# p0-001.net
KiCad netlist of a schematic drawn in EAGLE
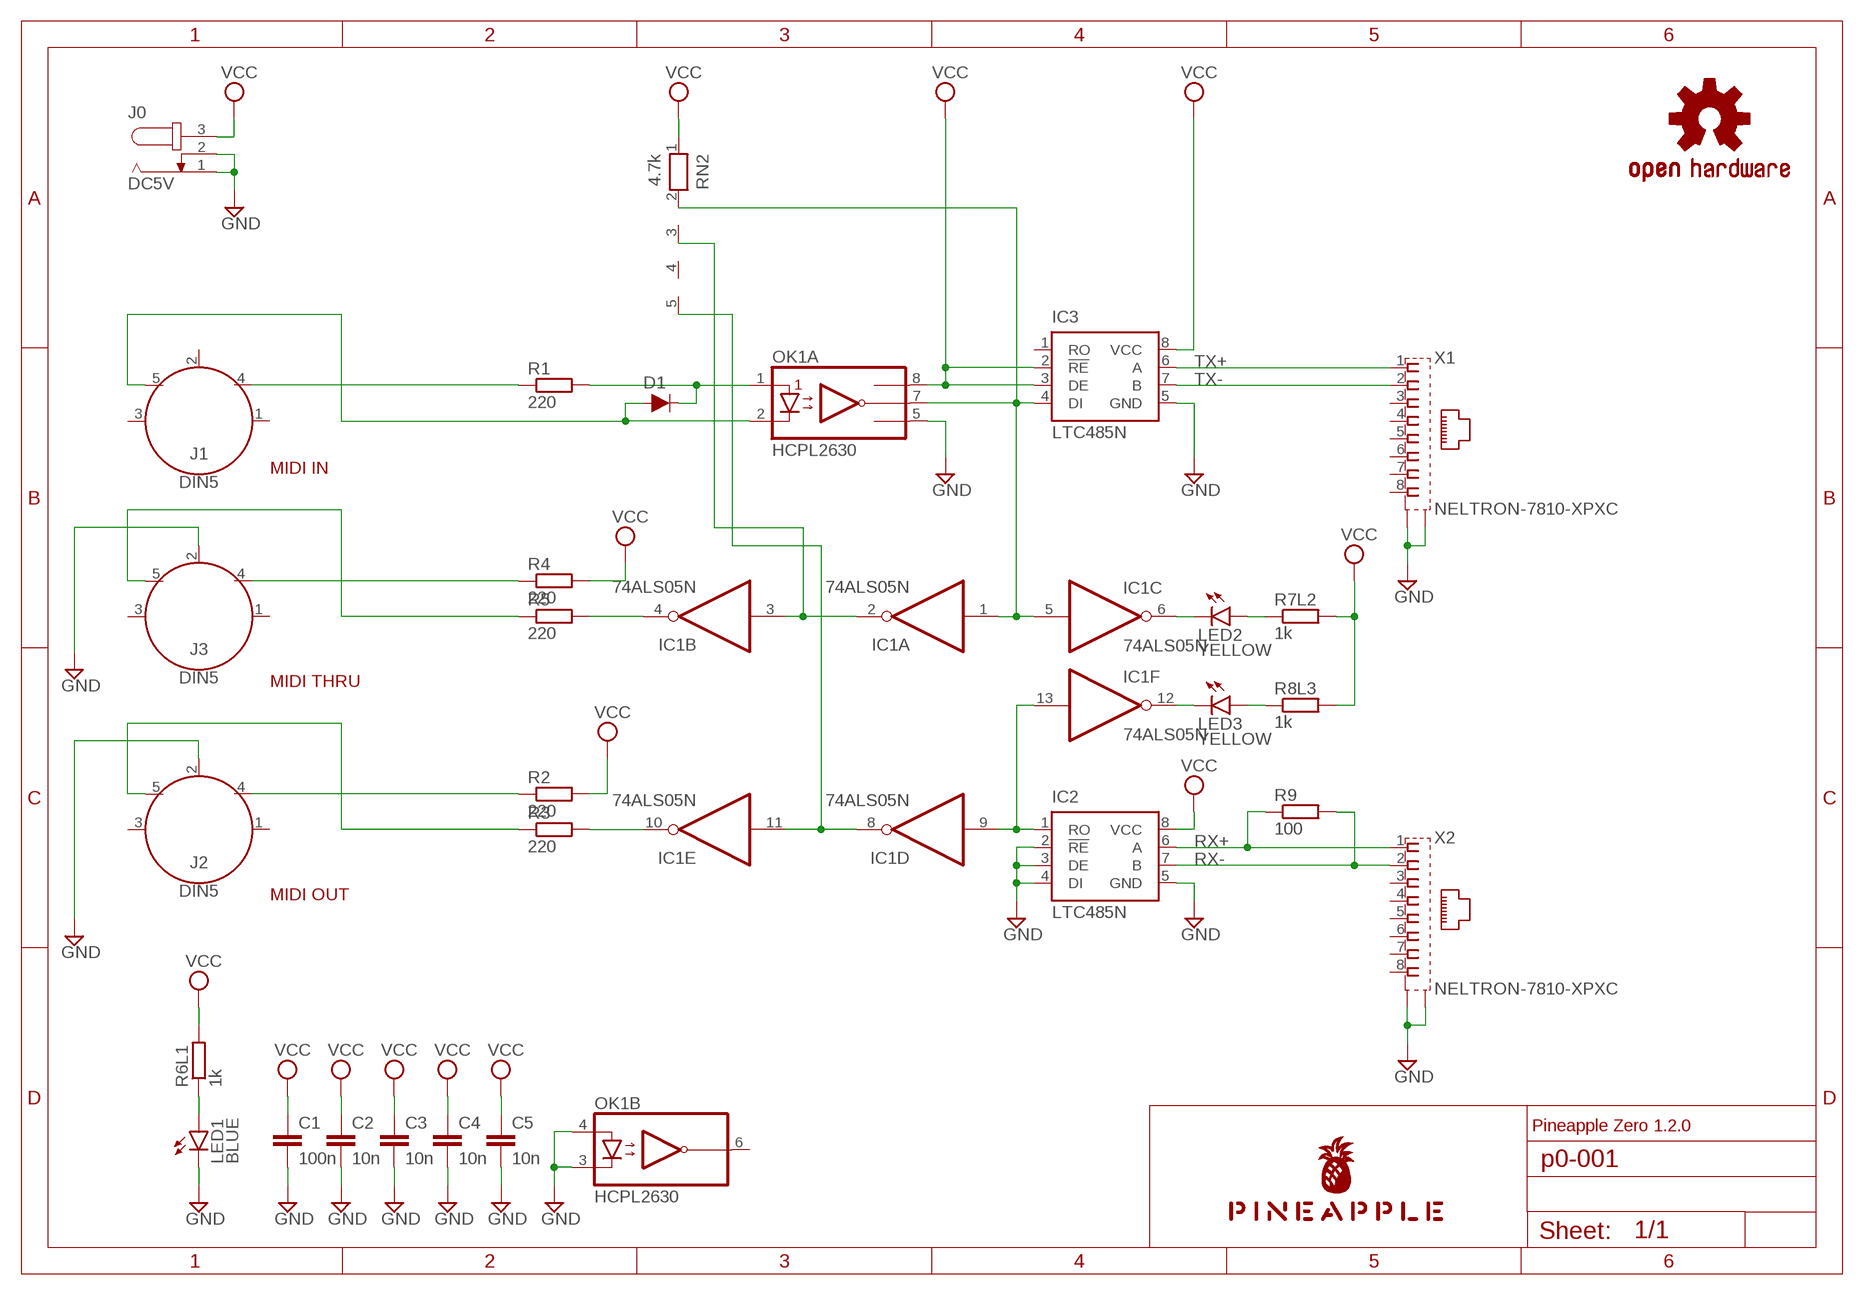
[diagram p0: schematic, sheet 1]

(export (version "E")
  (design (tool "Eeschema 10.0.6"))
  (components
    (comp (ref "C1")
      (value "100n")
      (footprint "eagle-import:C025-024X044")
      (libsource (lib "eagle-import") (part "C-EU025-024X044"))
    )
    (comp (ref "C2")
      (value "10n")
      (footprint "eagle-import:C025-024X044")
      (libsource (lib "eagle-import") (part "C-EU025-024X044"))
    )
    (comp (ref "C3")
      (value "10n")
      (footprint "eagle-import:C025-024X044")
      (libsource (lib "eagle-import") (part "C-EU025-024X044"))
    )
    (comp (ref "C4")
      (value "10n")
      (footprint "eagle-import:C025-024X044")
      (libsource (lib "eagle-import") (part "C-EU025-024X044"))
    )
    (comp (ref "C5")
      (value "10n")
      (footprint "eagle-import:C025-024X044")
      (libsource (lib "eagle-import") (part "C-EU025-024X044"))
    )
    (comp (ref "D1")
      (value "DIODE-1N4148")
      (footprint "eagle-import:DIODE-1N4148")
      (libsource (lib "eagle-import") (part "DIODE-1N4148"))
    )
    (comp (ref "IC1")
      (value "74ALS05N")
      (footprint "eagle-import:DIL14")
      (libsource (lib "eagle-import") (part "7405NALS"))
    )
    (comp (ref "IC2")
      (value "LTC485N")
      (footprint "eagle-import:DIL08")
      (libsource (lib "eagle-import") (part "LTC485N"))
    )
    (comp (ref "IC3")
      (value "LTC485N")
      (footprint "eagle-import:DIL08")
      (libsource (lib "eagle-import") (part "LTC485N"))
    )
    (comp (ref "J0")
      (value "DC5V")
      (footprint "eagle-import:SPC4077")
      (libsource (lib "eagle-import") (part "JACK-PLUG0"))
    )
    (comp (ref "J1")
      (value "DIN5")
      (footprint "eagle-import:DIN5-RA-PTH")
      (libsource (lib "eagle-import") (part "DIN5"))
    )
    (comp (ref "J2")
      (value "DIN5")
      (footprint "eagle-import:DIN5-RA-PTH")
      (libsource (lib "eagle-import") (part "DIN5"))
    )
    (comp (ref "J3")
      (value "DIN5")
      (footprint "eagle-import:DIN5-RA-PTH")
      (libsource (lib "eagle-import") (part "DIN5"))
    )
    (comp (ref "LED1")
      (value "BLUE")
      (footprint "eagle-import:LED3MM")
      (libsource (lib "eagle-import") (part "LED3MM"))
    )
    (comp (ref "LED2")
      (value "YELLOW")
      (footprint "eagle-import:LED3MM")
      (libsource (lib "eagle-import") (part "LED3MM"))
    )
    (comp (ref "LED3")
      (value "YELLOW")
      (footprint "eagle-import:LED3MM")
      (libsource (lib "eagle-import") (part "LED3MM"))
    )
    (comp (ref "LOGO1")
      (value "OSHW-LOGOS-COPPER")
      (footprint "eagle-import:OSHW-LOGO-S_COPPER")
      (libsource (lib "eagle-import") (part "OSHW-LOGOS-COPPER"))
    )
    (comp (ref "OK1")
      (value "HCPL2630")
      (footprint "eagle-import:DIL08")
      (fields (field (name "MF") "AGILENT TECHNOLOGIES") (field (name "MPN") "HCPL-2630-000E"))
      (libsource (lib "eagle-import") (part "HCPL2630"))
    )
    (comp (ref "R1")
      (value "220")
      (footprint "eagle-import:0204_5")
      (libsource (lib "eagle-import") (part "R-EU_0204/5"))
    )
    (comp (ref "R2")
      (value "220")
      (footprint "eagle-import:0204_5")
      (libsource (lib "eagle-import") (part "R-EU_0204/5"))
    )
    (comp (ref "R3")
      (value "220")
      (footprint "eagle-import:0204_5")
      (libsource (lib "eagle-import") (part "R-EU_0204/5"))
    )
    (comp (ref "R4")
      (value "220")
      (footprint "eagle-import:0204_5")
      (libsource (lib "eagle-import") (part "R-EU_0204/5"))
    )
    (comp (ref "R5")
      (value "220")
      (footprint "eagle-import:0204_5")
      (libsource (lib "eagle-import") (part "R-EU_0204/5"))
    )
    (comp (ref "R6L1")
      (value "1k")
      (footprint "eagle-import:0204_5")
      (libsource (lib "eagle-import") (part "R-EU_0204/5"))
    )
    (comp (ref "R7L2")
      (value "1k")
      (footprint "eagle-import:0204_5")
      (libsource (lib "eagle-import") (part "R-EU_0204/5"))
    )
    (comp (ref "R8L3")
      (value "1k")
      (footprint "eagle-import:0204_5")
      (libsource (lib "eagle-import") (part "R-EU_0204/5"))
    )
    (comp (ref "R9")
      (value "100")
      (footprint "eagle-import:0204_5")
      (libsource (lib "eagle-import") (part "R-EU_0204/5"))
    )
    (comp (ref "RN2")
      (value "4.7k")
      (footprint "eagle-import:RN-5")
      (libsource (lib "eagle-import") (part "RN04"))
    )
    (comp (ref "U$1")
      (value "PINEAPPLE450")
      (footprint "eagle-import:PINEAPPLE450")
      (libsource (lib "eagle-import") (part "PINEAPPLE450"))
    )
    (comp (ref "X1")
      (value "NELTRON-7810-XPXC")
      (footprint "eagle-import:NELTRON-7810-XPXC-FOOTPRINT")
      (libsource (lib "eagle-import") (part "NELTRON-7810-XPXC"))
    )
    (comp (ref "X2")
      (value "NELTRON-7810-XPXC")
      (footprint "eagle-import:NELTRON-7810-XPXC-FOOTPRINT")
      (libsource (lib "eagle-import") (part "NELTRON-7810-XPXC"))
    )
  )
  (nets
    (net (code "1") (name "/RX+") (class "Default")
      (node (ref "IC2") (pin "6") (pinfunction "A_6") (pintype "bidirectional"))
      (node (ref "R9") (pin "1") (pinfunction "1_1") (pintype "passive"))
      (node (ref "X2") (pin "1") (pinfunction "1_1") (pintype "passive"))
    )
    (net (code "2") (name "/RX-") (class "Default")
      (node (ref "IC2") (pin "7") (pinfunction "B_7") (pintype "bidirectional"))
      (node (ref "R9") (pin "2") (pinfunction "2_2") (pintype "passive"))
      (node (ref "X2") (pin "2") (pinfunction "2_2") (pintype "passive"))
    )
    (net (code "3") (name "/TX+") (class "Default")
      (node (ref "IC3") (pin "6") (pinfunction "A_6") (pintype "bidirectional"))
      (node (ref "X1") (pin "1") (pinfunction "1_1") (pintype "passive"))
    )
    (net (code "4") (name "/TX-") (class "Default")
      (node (ref "IC3") (pin "7") (pinfunction "B_7") (pintype "bidirectional"))
      (node (ref "X1") (pin "2") (pinfunction "2_2") (pintype "passive"))
    )
    (net (code "5") (name "GND") (class "Default")
      (node (ref "C1") (pin "2") (pinfunction "2_2") (pintype "passive"))
      (node (ref "C2") (pin "2") (pinfunction "2_2") (pintype "passive"))
      (node (ref "C3") (pin "2") (pinfunction "2_2") (pintype "passive"))
      (node (ref "C4") (pin "2") (pinfunction "2_2") (pintype "passive"))
      (node (ref "C5") (pin "2") (pinfunction "2_2") (pintype "passive"))
      (node (ref "IC2") (pin "2") (pinfunction "~{RE}_2") (pintype "input"))
      (node (ref "IC2") (pin "3") (pinfunction "DE_3") (pintype "input"))
      (node (ref "IC2") (pin "4") (pinfunction "DI_4") (pintype "input"))
      (node (ref "IC2") (pin "5") (pinfunction "GND_5") (pintype "input"))
      (node (ref "IC3") (pin "5") (pinfunction "GND_5") (pintype "input"))
      (node (ref "J0") (pin "1") (pinfunction "1_1") (pintype "passive"))
      (node (ref "J0") (pin "2") (pinfunction "2_2") (pintype "passive"))
      (node (ref "J2") (pin "2") (pinfunction "2_2") (pintype "bidirectional"))
      (node (ref "J3") (pin "2") (pinfunction "2_2") (pintype "bidirectional"))
      (node (ref "LED1") (pin "K") (pinfunction "C_K") (pintype "passive"))
      (node (ref "OK1") (pin "3") (pinfunction "C2_3") (pintype "passive"))
      (node (ref "OK1") (pin "4") (pinfunction "A2_4") (pintype "passive"))
      (node (ref "OK1") (pin "5") (pinfunction "GND_5") (pintype "passive"))
      (node (ref "X1") (pin "S1") (pinfunction "S1_S1") (pintype "passive"))
      (node (ref "X1") (pin "S2") (pinfunction "S2_S2") (pintype "passive"))
      (node (ref "X2") (pin "S1") (pinfunction "S1_S1") (pintype "passive"))
      (node (ref "X2") (pin "S2") (pinfunction "S2_S2") (pintype "passive"))
    )
    (net (code "6") (name "Net-(IC1A-I)") (class "Default")
      (node (ref "IC1") (pin "1") (pinfunction "I_1") (pintype "input"))
      (node (ref "IC1") (pin "5") (pinfunction "I_5") (pintype "input"))
      (node (ref "IC3") (pin "4") (pinfunction "DI_4") (pintype "input"))
      (node (ref "OK1") (pin "7") (pinfunction "VO1_7") (pintype "passive"))
      (node (ref "RN2") (pin "2") (pinfunction "2_2") (pintype "passive"))
    )
    (net (code "7") (name "Net-(IC1A-O)") (class "Default")
      (node (ref "IC1") (pin "2") (pinfunction "O_2") (pintype "open_collector"))
      (node (ref "IC1") (pin "3") (pinfunction "I_3") (pintype "input"))
      (node (ref "RN2") (pin "3") (pinfunction "3_3") (pintype "passive"))
    )
    (net (code "8") (name "Net-(IC1B-O)") (class "Default")
      (node (ref "IC1") (pin "4") (pinfunction "O_4") (pintype "open_collector"))
      (node (ref "R5") (pin "2") (pinfunction "2_2") (pintype "passive"))
    )
    (net (code "9") (name "Net-(IC1C-O)") (class "Default")
      (node (ref "IC1") (pin "6") (pinfunction "O_6") (pintype "open_collector"))
      (node (ref "LED2") (pin "K") (pinfunction "C_K") (pintype "passive"))
    )
    (net (code "10") (name "Net-(IC1D-I)") (class "Default")
      (node (ref "IC1") (pin "13") (pinfunction "I_13") (pintype "input"))
      (node (ref "IC1") (pin "9") (pinfunction "I_9") (pintype "input"))
      (node (ref "IC2") (pin "1") (pinfunction "RO_1") (pintype "output"))
    )
    (net (code "11") (name "Net-(IC1D-O)") (class "Default")
      (node (ref "IC1") (pin "11") (pinfunction "I_11") (pintype "input"))
      (node (ref "IC1") (pin "8") (pinfunction "O_8") (pintype "open_collector"))
      (node (ref "RN2") (pin "5") (pinfunction "5_5") (pintype "passive"))
    )
    (net (code "12") (name "Net-(IC1E-O)") (class "Default")
      (node (ref "IC1") (pin "10") (pinfunction "O_10") (pintype "open_collector"))
      (node (ref "R3") (pin "2") (pinfunction "2_2") (pintype "passive"))
    )
    (net (code "13") (name "Net-(IC1F-O)") (class "Default")
      (node (ref "IC1") (pin "12") (pinfunction "O_12") (pintype "open_collector"))
      (node (ref "LED3") (pin "K") (pinfunction "C_K") (pintype "passive"))
    )
    (net (code "14") (name "Net-(J1-Pad4)") (class "Default")
      (node (ref "J1") (pin "4") (pinfunction "4_4") (pintype "bidirectional"))
      (node (ref "R1") (pin "1") (pinfunction "1_1") (pintype "passive"))
    )
    (net (code "15") (name "Net-(J2-Pad4)") (class "Default")
      (node (ref "J2") (pin "4") (pinfunction "4_4") (pintype "bidirectional"))
      (node (ref "R2") (pin "1") (pinfunction "1_1") (pintype "passive"))
    )
    (net (code "16") (name "Net-(J2-Pad5)") (class "Default")
      (node (ref "J2") (pin "5") (pinfunction "5_5") (pintype "bidirectional"))
      (node (ref "R3") (pin "1") (pinfunction "1_1") (pintype "passive"))
    )
    (net (code "17") (name "Net-(J3-Pad4)") (class "Default")
      (node (ref "J3") (pin "4") (pinfunction "4_4") (pintype "bidirectional"))
      (node (ref "R4") (pin "1") (pinfunction "1_1") (pintype "passive"))
    )
    (net (code "18") (name "Net-(J3-Pad5)") (class "Default")
      (node (ref "J3") (pin "5") (pinfunction "5_5") (pintype "bidirectional"))
      (node (ref "R5") (pin "1") (pinfunction "1_1") (pintype "passive"))
    )
    (net (code "19") (name "Net-(LED1-PadA)") (class "Default")
      (node (ref "LED1") (pin "A") (pinfunction "A_A") (pintype "passive"))
      (node (ref "R6L1") (pin "1") (pinfunction "1_1") (pintype "passive"))
    )
    (net (code "20") (name "Net-(LED2-PadA)") (class "Default")
      (node (ref "LED2") (pin "A") (pinfunction "A_A") (pintype "passive"))
      (node (ref "R7L2") (pin "1") (pinfunction "1_1") (pintype "passive"))
    )
    (net (code "21") (name "Net-(LED3-PadA)") (class "Default")
      (node (ref "LED3") (pin "A") (pinfunction "A_A") (pintype "passive"))
      (node (ref "R8L3") (pin "1") (pinfunction "1_1") (pintype "passive"))
    )
    (net (code "22") (name "Net-(OK1A-A1)") (class "Default")
      (node (ref "D1") (pin "C") (pinfunction "C_C") (pintype "passive"))
      (node (ref "OK1") (pin "1") (pinfunction "A1_1") (pintype "passive"))
      (node (ref "R1") (pin "2") (pinfunction "2_2") (pintype "passive"))
    )
    (net (code "23") (name "Net-(OK1A-C1)") (class "Default")
      (node (ref "D1") (pin "A") (pinfunction "A_A") (pintype "passive"))
      (node (ref "J1") (pin "5") (pinfunction "5_5") (pintype "bidirectional"))
      (node (ref "OK1") (pin "2") (pinfunction "C1_2") (pintype "passive"))
    )
    (net (code "24") (name "VCC") (class "Default")
      (node (ref "C1") (pin "1") (pinfunction "1_1") (pintype "passive"))
      (node (ref "C2") (pin "1") (pinfunction "1_1") (pintype "passive"))
      (node (ref "C3") (pin "1") (pinfunction "1_1") (pintype "passive"))
      (node (ref "C4") (pin "1") (pinfunction "1_1") (pintype "passive"))
      (node (ref "C5") (pin "1") (pinfunction "1_1") (pintype "passive"))
      (node (ref "IC2") (pin "8") (pinfunction "VCC_8") (pintype "input"))
      (node (ref "IC3") (pin "2") (pinfunction "~{RE}_2") (pintype "input"))
      (node (ref "IC3") (pin "3") (pinfunction "DE_3") (pintype "input"))
      (node (ref "IC3") (pin "8") (pinfunction "VCC_8") (pintype "input"))
      (node (ref "J0") (pin "3") (pinfunction "3_3") (pintype "passive"))
      (node (ref "OK1") (pin "8") (pinfunction "VCC_8") (pintype "passive"))
      (node (ref "R2") (pin "2") (pinfunction "2_2") (pintype "passive"))
      (node (ref "R4") (pin "2") (pinfunction "2_2") (pintype "passive"))
      (node (ref "R6L1") (pin "2") (pinfunction "2_2") (pintype "passive"))
      (node (ref "R7L2") (pin "2") (pinfunction "2_2") (pintype "passive"))
      (node (ref "R8L3") (pin "2") (pinfunction "2_2") (pintype "passive"))
      (node (ref "RN2") (pin "1") (pinfunction "1_1") (pintype "passive"))
    )
    (net (code "25") (name "unconnected-(IC3-RO-Pad1)") (class "Default")
      (node (ref "IC3") (pin "1") (pinfunction "RO_1") (pintype "output"))
    )
    (net (code "26") (name "unconnected-(J1-Pad1)") (class "Default")
      (node (ref "J1") (pin "1") (pinfunction "1_1") (pintype "bidirectional"))
    )
    (net (code "27") (name "unconnected-(J1-Pad2)") (class "Default")
      (node (ref "J1") (pin "2") (pinfunction "2_2") (pintype "bidirectional"))
    )
    (net (code "28") (name "unconnected-(J1-Pad3)") (class "Default")
      (node (ref "J1") (pin "3") (pinfunction "3_3") (pintype "bidirectional"))
    )
    (net (code "29") (name "unconnected-(J2-Pad1)") (class "Default")
      (node (ref "J2") (pin "1") (pinfunction "1_1") (pintype "bidirectional"))
    )
    (net (code "30") (name "unconnected-(J2-Pad3)") (class "Default")
      (node (ref "J2") (pin "3") (pinfunction "3_3") (pintype "bidirectional"))
    )
    (net (code "31") (name "unconnected-(J3-Pad1)") (class "Default")
      (node (ref "J3") (pin "1") (pinfunction "1_1") (pintype "bidirectional"))
    )
    (net (code "32") (name "unconnected-(J3-Pad3)") (class "Default")
      (node (ref "J3") (pin "3") (pinfunction "3_3") (pintype "bidirectional"))
    )
    (net (code "33") (name "unconnected-(OK1B-VO2-Pad6)") (class "Default")
      (node (ref "OK1") (pin "6") (pinfunction "VO2_6") (pintype "passive"))
    )
    (net (code "34") (name "unconnected-(RN2-Pad4)") (class "Default")
      (node (ref "RN2") (pin "4") (pinfunction "4_4") (pintype "passive"))
    )
    (net (code "35") (name "unconnected-(X1-Pad3)") (class "Default")
      (node (ref "X1") (pin "3") (pinfunction "3_3") (pintype "passive"))
    )
    (net (code "36") (name "unconnected-(X1-Pad4)") (class "Default")
      (node (ref "X1") (pin "4") (pinfunction "4_4") (pintype "passive"))
    )
    (net (code "37") (name "unconnected-(X1-Pad5)") (class "Default")
      (node (ref "X1") (pin "5") (pinfunction "5_5") (pintype "passive"))
    )
    (net (code "38") (name "unconnected-(X1-Pad6)") (class "Default")
      (node (ref "X1") (pin "6") (pinfunction "6_6") (pintype "passive"))
    )
    (net (code "39") (name "unconnected-(X1-Pad7)") (class "Default")
      (node (ref "X1") (pin "7") (pinfunction "7_7") (pintype "passive"))
    )
    (net (code "40") (name "unconnected-(X1-Pad8)") (class "Default")
      (node (ref "X1") (pin "8") (pinfunction "8_8") (pintype "passive"))
    )
    (net (code "41") (name "unconnected-(X2-Pad3)") (class "Default")
      (node (ref "X2") (pin "3") (pinfunction "3_3") (pintype "passive"))
    )
    (net (code "42") (name "unconnected-(X2-Pad4)") (class "Default")
      (node (ref "X2") (pin "4") (pinfunction "4_4") (pintype "passive"))
    )
    (net (code "43") (name "unconnected-(X2-Pad5)") (class "Default")
      (node (ref "X2") (pin "5") (pinfunction "5_5") (pintype "passive"))
    )
    (net (code "44") (name "unconnected-(X2-Pad6)") (class "Default")
      (node (ref "X2") (pin "6") (pinfunction "6_6") (pintype "passive"))
    )
    (net (code "45") (name "unconnected-(X2-Pad7)") (class "Default")
      (node (ref "X2") (pin "7") (pinfunction "7_7") (pintype "passive"))
    )
    (net (code "46") (name "unconnected-(X2-Pad8)") (class "Default")
      (node (ref "X2") (pin "8") (pinfunction "8_8") (pintype "passive"))
    )
  )
)
